# PROB_S7CAS_Clock.net
KiCad netlist of a schematic drawn in Altium Designer
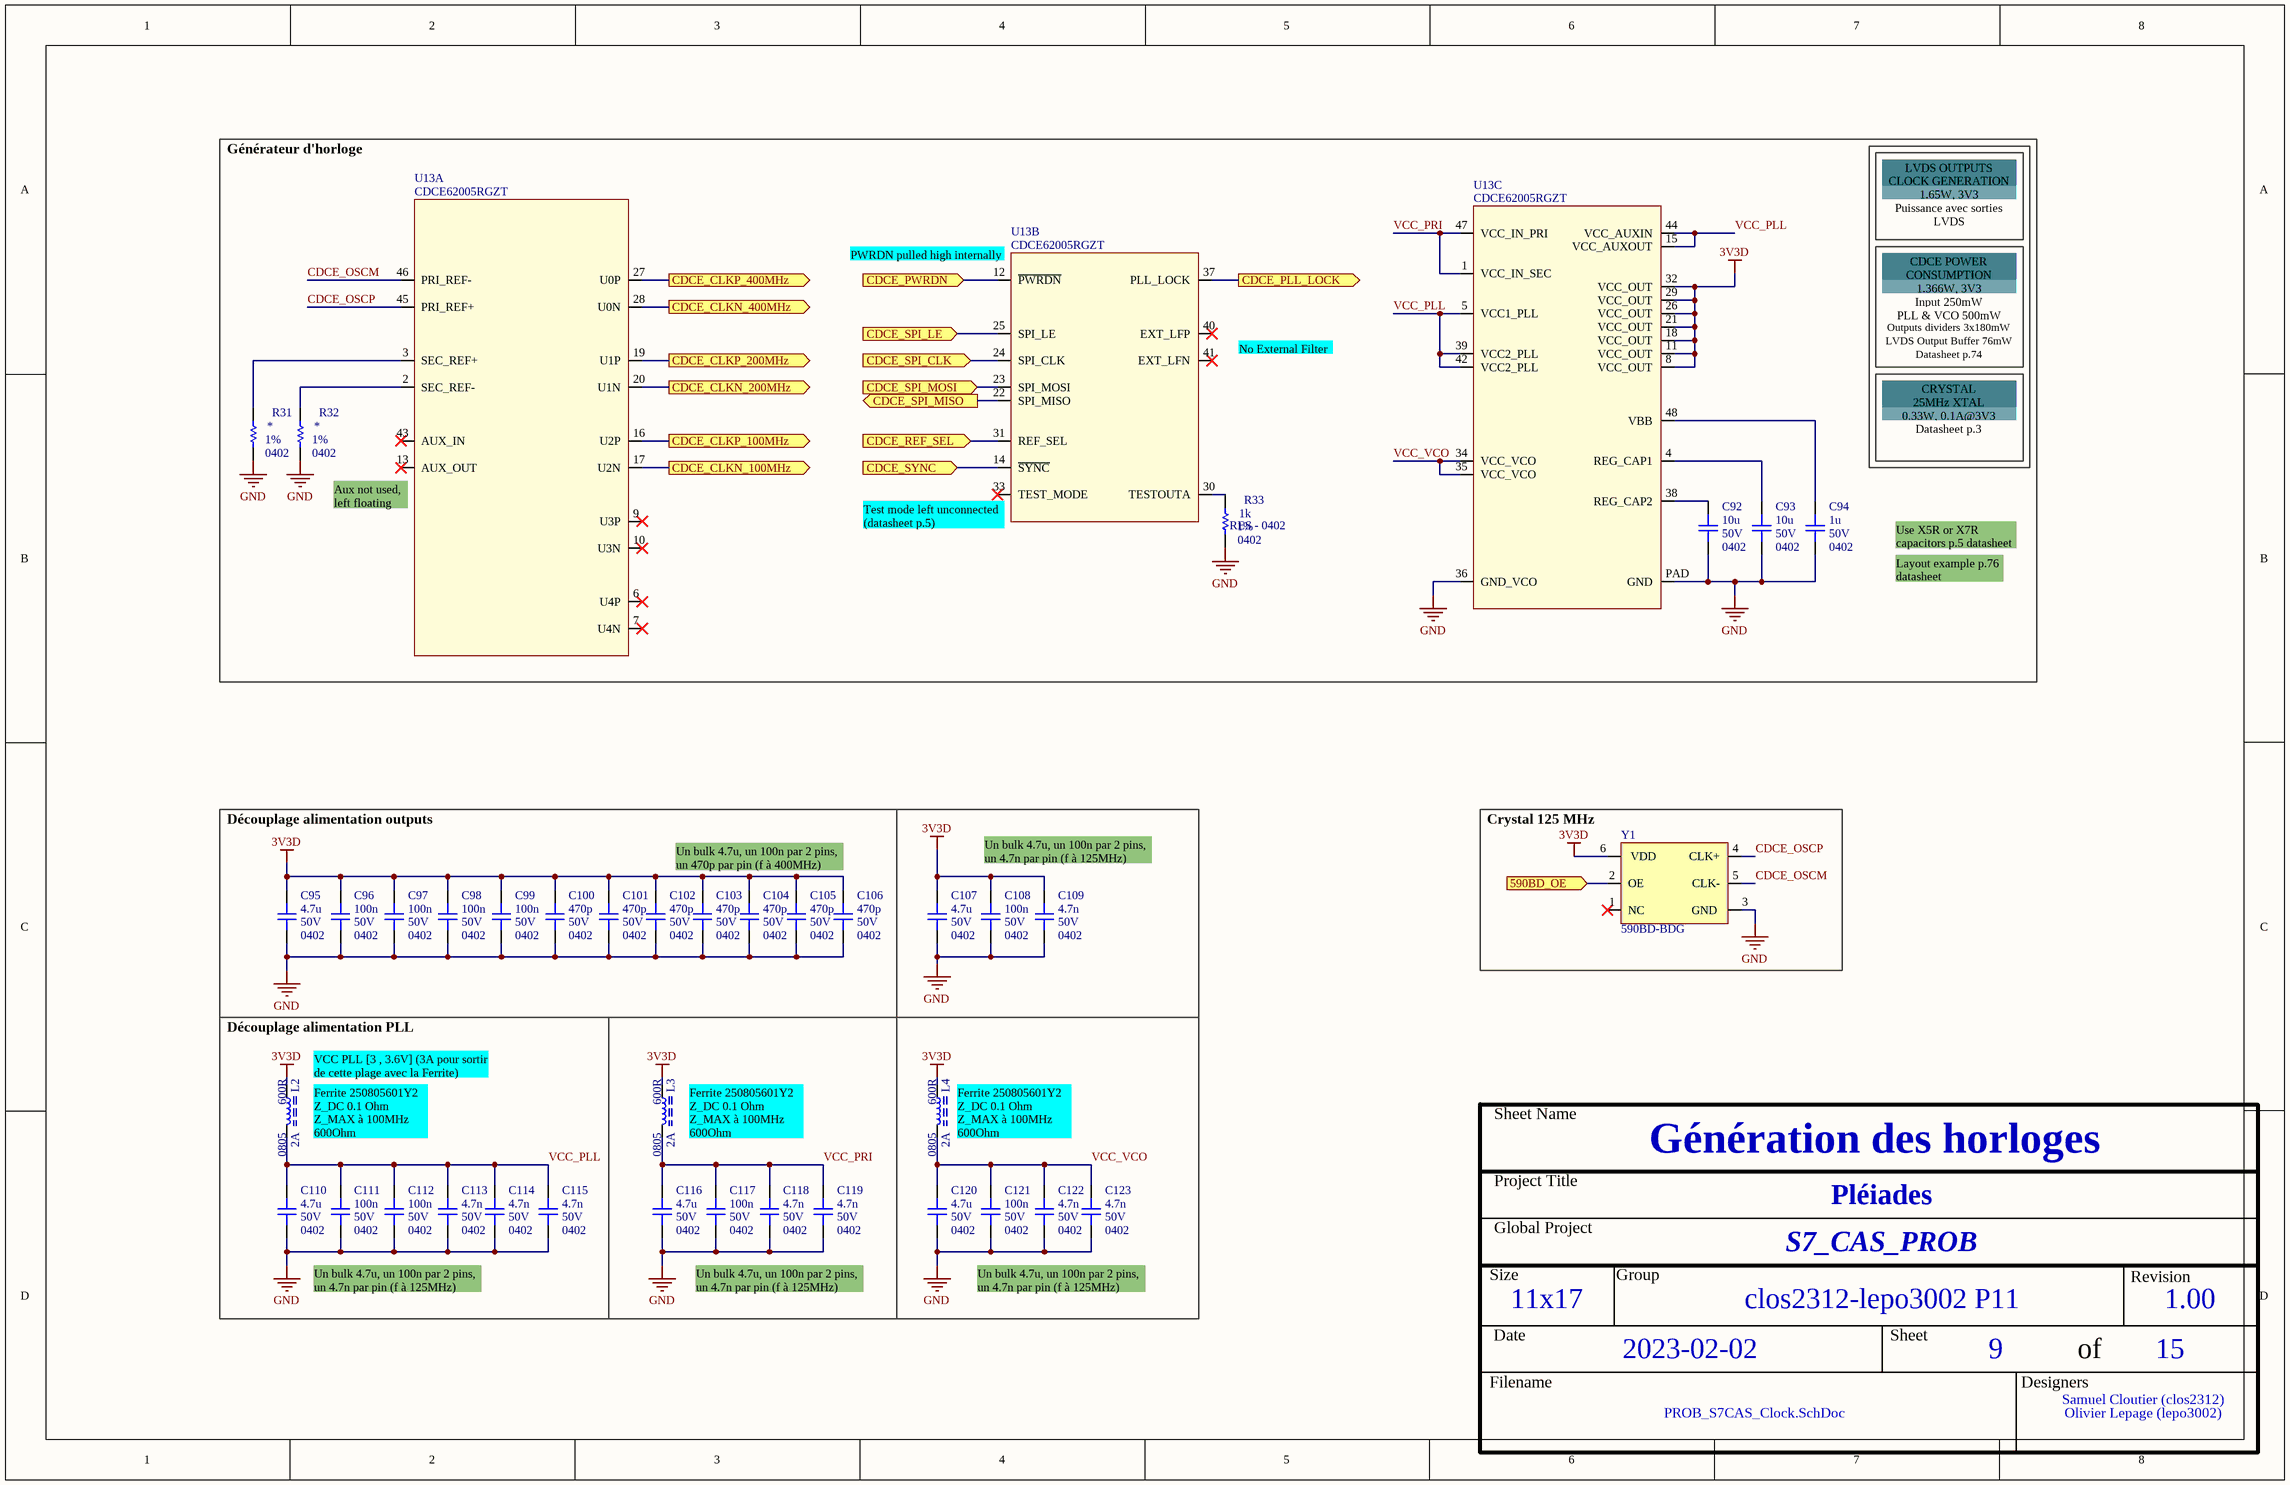
[diagram p0: PROB_S7CAS_Clock.SchDoc]

(export (version "E")
  (design (tool "Eeschema 10.0.6"))
  (components
    (comp (ref "C92")
      (value "10u")
      (footprint "CAP_0402")
      (description "CAP - 0402")
      (fields
        (field (name "VOLTAGE") "50V")
        (field (name "PACKAGE") "0402")
        (field (name "CREATEDBY") "Jonathan Bouchard")
      )
      (libsource (lib "S7CAS_LIB2021") (part "CAP - 0402"))
    )
    (comp (ref "C93")
      (value "10u")
      (footprint "CAP_0402")
      (description "CAP - 0402")
      (fields
        (field (name "VOLTAGE") "50V")
        (field (name "PACKAGE") "0402")
        (field (name "CREATEDBY") "Jonathan Bouchard")
      )
      (libsource (lib "S7CAS_LIB2021") (part "CAP - 0402"))
    )
    (comp (ref "C94")
      (value "1u")
      (footprint "CAP_0402")
      (description "CAP - 0402")
      (fields
        (field (name "VOLTAGE") "50V")
        (field (name "PACKAGE") "0402")
        (field (name "CREATEDBY") "Jonathan Bouchard")
      )
      (libsource (lib "S7CAS_LIB2021") (part "CAP - 0402"))
    )
    (comp (ref "C95")
      (value "4.7u")
      (footprint "CAP_0402")
      (description "CAP - 0402")
      (fields
        (field (name "VOLTAGE") "50V")
        (field (name "PACKAGE") "0402")
        (field (name "CREATEDBY") "Jonathan Bouchard")
      )
      (libsource (lib "S7CAS_LIB2021") (part "CAP - 0402"))
    )
    (comp (ref "C96")
      (value "100n")
      (footprint "CAP_0402")
      (description "CAP - 0402")
      (fields
        (field (name "VOLTAGE") "50V")
        (field (name "PACKAGE") "0402")
        (field (name "CREATEDBY") "Jonathan Bouchard")
      )
      (libsource (lib "S7CAS_LIB2021") (part "CAP - 0402"))
    )
    (comp (ref "C97")
      (value "100n")
      (footprint "CAP_0402")
      (description "CAP - 0402")
      (fields
        (field (name "VOLTAGE") "50V")
        (field (name "PACKAGE") "0402")
        (field (name "CREATEDBY") "Jonathan Bouchard")
      )
      (libsource (lib "S7CAS_LIB2021") (part "CAP - 0402"))
    )
    (comp (ref "C98")
      (value "100n")
      (footprint "CAP_0402")
      (description "CAP - 0402")
      (fields
        (field (name "VOLTAGE") "50V")
        (field (name "PACKAGE") "0402")
        (field (name "CREATEDBY") "Jonathan Bouchard")
      )
      (libsource (lib "S7CAS_LIB2021") (part "CAP - 0402"))
    )
    (comp (ref "C99")
      (value "100n")
      (footprint "CAP_0402")
      (description "CAP - 0402")
      (fields
        (field (name "VOLTAGE") "50V")
        (field (name "PACKAGE") "0402")
        (field (name "CREATEDBY") "Jonathan Bouchard")
      )
      (libsource (lib "S7CAS_LIB2021") (part "CAP - 0402"))
    )
    (comp (ref "C100")
      (value "470p")
      (footprint "CAP_0402")
      (description "CAP - 0402")
      (fields
        (field (name "VOLTAGE") "50V")
        (field (name "PACKAGE") "0402")
        (field (name "CREATEDBY") "Jonathan Bouchard")
      )
      (libsource (lib "S7CAS_LIB2021") (part "CAP - 0402"))
    )
    (comp (ref "C101")
      (value "470p")
      (footprint "CAP_0402")
      (description "CAP - 0402")
      (fields
        (field (name "VOLTAGE") "50V")
        (field (name "PACKAGE") "0402")
        (field (name "CREATEDBY") "Jonathan Bouchard")
      )
      (libsource (lib "S7CAS_LIB2021") (part "CAP - 0402"))
    )
    (comp (ref "C102")
      (value "470p")
      (footprint "CAP_0402")
      (description "CAP - 0402")
      (fields
        (field (name "VOLTAGE") "50V")
        (field (name "PACKAGE") "0402")
        (field (name "CREATEDBY") "Jonathan Bouchard")
      )
      (libsource (lib "S7CAS_LIB2021") (part "CAP - 0402"))
    )
    (comp (ref "C103")
      (value "470p")
      (footprint "CAP_0402")
      (description "CAP - 0402")
      (fields
        (field (name "VOLTAGE") "50V")
        (field (name "PACKAGE") "0402")
        (field (name "CREATEDBY") "Jonathan Bouchard")
      )
      (libsource (lib "S7CAS_LIB2021") (part "CAP - 0402"))
    )
    (comp (ref "C104")
      (value "470p")
      (footprint "CAP_0402")
      (description "CAP - 0402")
      (fields
        (field (name "VOLTAGE") "50V")
        (field (name "PACKAGE") "0402")
        (field (name "CREATEDBY") "Jonathan Bouchard")
      )
      (libsource (lib "S7CAS_LIB2021") (part "CAP - 0402"))
    )
    (comp (ref "C105")
      (value "470p")
      (footprint "CAP_0402")
      (description "CAP - 0402")
      (fields
        (field (name "VOLTAGE") "50V")
        (field (name "PACKAGE") "0402")
        (field (name "CREATEDBY") "Jonathan Bouchard")
      )
      (libsource (lib "S7CAS_LIB2021") (part "CAP - 0402"))
    )
    (comp (ref "C106")
      (value "470p")
      (footprint "CAP_0402")
      (description "CAP - 0402")
      (fields
        (field (name "VOLTAGE") "50V")
        (field (name "PACKAGE") "0402")
        (field (name "CREATEDBY") "Jonathan Bouchard")
      )
      (libsource (lib "S7CAS_LIB2021") (part "CAP - 0402"))
    )
    (comp (ref "C107")
      (value "4.7u")
      (footprint "CAP_0402")
      (description "CAP - 0402")
      (fields
        (field (name "VOLTAGE") "50V")
        (field (name "PACKAGE") "0402")
        (field (name "CREATEDBY") "Jonathan Bouchard")
      )
      (libsource (lib "S7CAS_LIB2021") (part "CAP - 0402"))
    )
    (comp (ref "C108")
      (value "100n")
      (footprint "CAP_0402")
      (description "CAP - 0402")
      (fields
        (field (name "VOLTAGE") "50V")
        (field (name "PACKAGE") "0402")
        (field (name "CREATEDBY") "Jonathan Bouchard")
      )
      (libsource (lib "S7CAS_LIB2021") (part "CAP - 0402"))
    )
    (comp (ref "C109")
      (value "4.7n")
      (footprint "CAP_0402")
      (description "CAP - 0402")
      (fields
        (field (name "VOLTAGE") "50V")
        (field (name "PACKAGE") "0402")
        (field (name "CREATEDBY") "Jonathan Bouchard")
      )
      (libsource (lib "S7CAS_LIB2021") (part "CAP - 0402"))
    )
    (comp (ref "C110")
      (value "4.7u")
      (footprint "CAP_0402")
      (description "CAP - 0402")
      (fields
        (field (name "VOLTAGE") "50V")
        (field (name "PACKAGE") "0402")
        (field (name "CREATEDBY") "Jonathan Bouchard")
      )
      (libsource (lib "S7CAS_LIB2021") (part "CAP - 0402"))
    )
    (comp (ref "C111")
      (value "100n")
      (footprint "CAP_0402")
      (description "CAP - 0402")
      (fields
        (field (name "VOLTAGE") "50V")
        (field (name "PACKAGE") "0402")
        (field (name "CREATEDBY") "Jonathan Bouchard")
      )
      (libsource (lib "S7CAS_LIB2021") (part "CAP - 0402"))
    )
    (comp (ref "C112")
      (value "100n")
      (footprint "CAP_0402")
      (description "CAP - 0402")
      (fields
        (field (name "VOLTAGE") "50V")
        (field (name "PACKAGE") "0402")
        (field (name "CREATEDBY") "Jonathan Bouchard")
      )
      (libsource (lib "S7CAS_LIB2021") (part "CAP - 0402"))
    )
    (comp (ref "C113")
      (value "4.7n")
      (footprint "CAP_0402")
      (description "CAP - 0402")
      (fields
        (field (name "VOLTAGE") "50V")
        (field (name "PACKAGE") "0402")
        (field (name "CREATEDBY") "Jonathan Bouchard")
      )
      (libsource (lib "S7CAS_LIB2021") (part "CAP - 0402"))
    )
    (comp (ref "C114")
      (value "4.7n")
      (footprint "CAP_0402")
      (description "CAP - 0402")
      (fields
        (field (name "VOLTAGE") "50V")
        (field (name "PACKAGE") "0402")
        (field (name "CREATEDBY") "Jonathan Bouchard")
      )
      (libsource (lib "S7CAS_LIB2021") (part "CAP - 0402"))
    )
    (comp (ref "C115")
      (value "4.7n")
      (footprint "CAP_0402")
      (description "CAP - 0402")
      (fields
        (field (name "VOLTAGE") "50V")
        (field (name "PACKAGE") "0402")
        (field (name "CREATEDBY") "Jonathan Bouchard")
      )
      (libsource (lib "S7CAS_LIB2021") (part "CAP - 0402"))
    )
    (comp (ref "C116")
      (value "4.7u")
      (footprint "CAP_0402")
      (description "CAP - 0402")
      (fields
        (field (name "VOLTAGE") "50V")
        (field (name "PACKAGE") "0402")
        (field (name "CREATEDBY") "Jonathan Bouchard")
      )
      (libsource (lib "S7CAS_LIB2021") (part "CAP - 0402"))
    )
    (comp (ref "C117")
      (value "100n")
      (footprint "CAP_0402")
      (description "CAP - 0402")
      (fields
        (field (name "VOLTAGE") "50V")
        (field (name "PACKAGE") "0402")
        (field (name "CREATEDBY") "Jonathan Bouchard")
      )
      (libsource (lib "S7CAS_LIB2021") (part "CAP - 0402"))
    )
    (comp (ref "C118")
      (value "4.7n")
      (footprint "CAP_0402")
      (description "CAP - 0402")
      (fields
        (field (name "VOLTAGE") "50V")
        (field (name "PACKAGE") "0402")
        (field (name "CREATEDBY") "Jonathan Bouchard")
      )
      (libsource (lib "S7CAS_LIB2021") (part "CAP - 0402"))
    )
    (comp (ref "C119")
      (value "4.7n")
      (footprint "CAP_0402")
      (description "CAP - 0402")
      (fields
        (field (name "VOLTAGE") "50V")
        (field (name "PACKAGE") "0402")
        (field (name "CREATEDBY") "Jonathan Bouchard")
      )
      (libsource (lib "S7CAS_LIB2021") (part "CAP - 0402"))
    )
    (comp (ref "C120")
      (value "4.7u")
      (footprint "CAP_0402")
      (description "CAP - 0402")
      (fields
        (field (name "VOLTAGE") "50V")
        (field (name "PACKAGE") "0402")
        (field (name "CREATEDBY") "Jonathan Bouchard")
      )
      (libsource (lib "S7CAS_LIB2021") (part "CAP - 0402"))
    )
    (comp (ref "C121")
      (value "100n")
      (footprint "CAP_0402")
      (description "CAP - 0402")
      (fields
        (field (name "VOLTAGE") "50V")
        (field (name "PACKAGE") "0402")
        (field (name "CREATEDBY") "Jonathan Bouchard")
      )
      (libsource (lib "S7CAS_LIB2021") (part "CAP - 0402"))
    )
    (comp (ref "C122")
      (value "4.7n")
      (footprint "CAP_0402")
      (description "CAP - 0402")
      (fields
        (field (name "VOLTAGE") "50V")
        (field (name "PACKAGE") "0402")
        (field (name "CREATEDBY") "Jonathan Bouchard")
      )
      (libsource (lib "S7CAS_LIB2021") (part "CAP - 0402"))
    )
    (comp (ref "C123")
      (value "4.7n")
      (footprint "CAP_0402")
      (description "CAP - 0402")
      (fields
        (field (name "VOLTAGE") "50V")
        (field (name "PACKAGE") "0402")
        (field (name "CREATEDBY") "Jonathan Bouchard")
      )
      (libsource (lib "S7CAS_LIB2021") (part "CAP - 0402"))
    )
    (comp (ref "L2")
      (value "600R")
      (footprint "FER_0402")
      (description "FER - 0402")
      (fields
        (field (name "CURRENT") "2A")
        (field (name "PACKAGE") "0805")
        (field (name "CREATEDBY") "Jonathan Bouchard")
      )
      (libsource (lib "S7CAS_LIB2021") (part "FER - 0402"))
    )
    (comp (ref "L3")
      (value "600R")
      (footprint "FER_0402")
      (description "FER - 0402")
      (fields
        (field (name "CURRENT") "2A")
        (field (name "PACKAGE") "0805")
        (field (name "CREATEDBY") "Jonathan Bouchard")
      )
      (libsource (lib "S7CAS_LIB2021") (part "FER - 0402"))
    )
    (comp (ref "L4")
      (value "600R")
      (footprint "FER_0402")
      (description "FER - 0402")
      (fields
        (field (name "CURRENT") "2A")
        (field (name "PACKAGE") "0805")
        (field (name "CREATEDBY") "Jonathan Bouchard")
      )
      (libsource (lib "S7CAS_LIB2021") (part "FER - 0402"))
    )
    (comp (ref "R31")
      (value "RES - 0402")
      (footprint "RES_0402")
      (fields
        (field (name "VOLTAGE") "50V")
        (field (name "POWER") "1/16W")
        (field (name "PACKAGE") "0402")
        (field (name "PRECISION") "1%")
        (field (name "ALTIUM_VALUE") "*")
        (field (name "CREATEDBY") "Jonathan Bouchard")
      )
      (libsource (lib "S7CAS_LIB2021") (part "RES - 0402"))
    )
    (comp (ref "R32")
      (value "RES - 0402")
      (footprint "RES_0402")
      (fields
        (field (name "VOLTAGE") "50V")
        (field (name "POWER") "1/16W")
        (field (name "PACKAGE") "0402")
        (field (name "PRECISION") "1%")
        (field (name "ALTIUM_VALUE") "*")
        (field (name "CREATEDBY") "Jonathan Bouchard")
      )
      (libsource (lib "S7CAS_LIB2021") (part "RES - 0402"))
    )
    (comp (ref "R33")
      (value "RES - 0402")
      (footprint "RES_0402")
      (fields
        (field (name "PACKAGE") "0402")
        (field (name "PRECISION") "1%")
        (field (name "ALTIUM_VALUE") "1k")
        (field (name "VOLTAGE") "50V")
        (field (name "POWER") "1/16W")
        (field (name "CREATEDBY") "Jonathan Bouchard")
      )
      (libsource (lib "Université de Sherbrooke") (part "RES - 1210"))
    )
    (comp (ref "U13")
      (value "CDCE62005RGZT")
      (footprint "TIM_CDCE62005RGZT")
      (description "TIM - CLK SYNTH JITTER CLEANER 3:5 - QFN-48")
      (fields
        (field (name "VOLTAGE") "3 V ~ 3.6 V")
        (field (name "MFG") "Texas Instruments")
        (field (name "CREATEDBY") "Jonathan Bouchard")
      )
      (libsource (lib "S7CAS_LIB2021") (part "TIM_CDCE62005RGZT"))
    )
    (comp (ref "Y1")
      (value "590BD-BDG")
      (footprint "OSC_590BD-BDG")
      (description "TIM - OSC PROG 125MHz ~ 214.999MHz LVDS 3.3V 7PPM EN/DS - 6-SMD")
      (fields
        (field (name "CREATEDBY/DATE") "from 590BD-CDG")
        (field (name "VERIFIEDBY") "Caroline Paulin / 3/10/2019")
      )
      (libsource (lib "S7CAS_LIB2021") (part "OSC_590BD-BDG"))
    )
  )
  (nets
    (net (code "1") (name "/590BD_OE") (class "Default")
      (node (ref "Y1") (pin "2") (pinfunction "OE_2") (pintype "passive"))
    )
    (net (code "2") (name "/CDCE_CLKN_100MHz") (class "Default")
      (node (ref "U13") (pin "17") (pinfunction "U2N_17") (pintype "passive"))
    )
    (net (code "3") (name "/CDCE_CLKN_200MHz") (class "Default")
      (node (ref "U13") (pin "20") (pinfunction "U1N_20") (pintype "passive"))
    )
    (net (code "4") (name "/CDCE_CLKN_400MHz") (class "Default")
      (node (ref "U13") (pin "28") (pinfunction "U0N_28") (pintype "passive"))
    )
    (net (code "5") (name "/CDCE_CLKP_100MHz") (class "Default")
      (node (ref "U13") (pin "16") (pinfunction "U2P_16") (pintype "passive"))
    )
    (net (code "6") (name "/CDCE_CLKP_200MHz") (class "Default")
      (node (ref "U13") (pin "19") (pinfunction "U1P_19") (pintype "passive"))
    )
    (net (code "7") (name "/CDCE_CLKP_400MHz") (class "Default")
      (node (ref "U13") (pin "27") (pinfunction "U0P_27") (pintype "passive"))
    )
    (net (code "8") (name "/CDCE_OSCM") (class "Default")
      (node (ref "U13") (pin "46") (pinfunction "PRI_REF-_46") (pintype "passive"))
      (node (ref "Y1") (pin "5") (pinfunction "CLK-_5") (pintype "passive"))
    )
    (net (code "9") (name "/CDCE_OSCP") (class "Default")
      (node (ref "U13") (pin "45") (pinfunction "PRI_REF+_45") (pintype "passive"))
      (node (ref "Y1") (pin "4") (pinfunction "CLK+_4") (pintype "passive"))
    )
    (net (code "10") (name "/CDCE_PLL_LOCK") (class "Default")
      (node (ref "U13") (pin "37") (pinfunction "PLL_LOCK_37") (pintype "passive"))
    )
    (net (code "11") (name "/CDCE_PWRDN") (class "Default")
      (node (ref "U13") (pin "12") (pinfunction "~{PWRDN}_12") (pintype "passive"))
    )
    (net (code "12") (name "/CDCE_REF_SEL") (class "Default")
      (node (ref "U13") (pin "31") (pinfunction "REF_SEL_31") (pintype "passive"))
    )
    (net (code "13") (name "/CDCE_SPI_CLK") (class "Default")
      (node (ref "U13") (pin "24") (pinfunction "SPI_CLK_24") (pintype "passive"))
    )
    (net (code "14") (name "/CDCE_SPI_LE") (class "Default")
      (node (ref "U13") (pin "25") (pinfunction "SPI_LE_25") (pintype "passive"))
    )
    (net (code "15") (name "/CDCE_SPI_MISO") (class "Default")
      (node (ref "U13") (pin "22") (pinfunction "SPI_MISO_22") (pintype "passive"))
    )
    (net (code "16") (name "/CDCE_SPI_MOSI") (class "Default")
      (node (ref "U13") (pin "23") (pinfunction "SPI_MOSI_23") (pintype "passive"))
    )
    (net (code "17") (name "/CDCE_SYNC") (class "Default")
      (node (ref "U13") (pin "14") (pinfunction "~{SYNC}_14") (pintype "passive"))
    )
    (net (code "18") (name "/VCC_PLL") (class "Default")
      (node (ref "C110") (pin "2") (pinfunction "2_2") (pintype "passive"))
      (node (ref "C111") (pin "2") (pinfunction "2_2") (pintype "passive"))
      (node (ref "C112") (pin "2") (pinfunction "2_2") (pintype "passive"))
      (node (ref "C113") (pin "2") (pinfunction "2_2") (pintype "passive"))
      (node (ref "C114") (pin "2") (pinfunction "2_2") (pintype "passive"))
      (node (ref "C115") (pin "2") (pinfunction "2_2") (pintype "passive"))
      (node (ref "L2") (pin "1") (pinfunction "1_1") (pintype "passive"))
      (node (ref "U13") (pin "15") (pinfunction "VCC_AUXOUT_15") (pintype "passive"))
      (node (ref "U13") (pin "39") (pinfunction "VCC2_PLL_39") (pintype "passive"))
      (node (ref "U13") (pin "42") (pinfunction "VCC2_PLL_42") (pintype "passive"))
      (node (ref "U13") (pin "44") (pinfunction "VCC_AUXIN_44") (pintype "passive"))
      (node (ref "U13") (pin "5") (pinfunction "VCC1_PLL_5") (pintype "passive"))
    )
    (net (code "19") (name "/VCC_PRI") (class "Default")
      (node (ref "C116") (pin "2") (pinfunction "2_2") (pintype "passive"))
      (node (ref "C117") (pin "2") (pinfunction "2_2") (pintype "passive"))
      (node (ref "C118") (pin "2") (pinfunction "2_2") (pintype "passive"))
      (node (ref "C119") (pin "2") (pinfunction "2_2") (pintype "passive"))
      (node (ref "L3") (pin "1") (pinfunction "1_1") (pintype "passive"))
      (node (ref "U13") (pin "1") (pinfunction "VCC_IN_SEC_1") (pintype "passive"))
      (node (ref "U13") (pin "47") (pinfunction "VCC_IN_PRI_47") (pintype "passive"))
    )
    (net (code "20") (name "/VCC_VCO") (class "Default")
      (node (ref "C120") (pin "2") (pinfunction "2_2") (pintype "passive"))
      (node (ref "C121") (pin "2") (pinfunction "2_2") (pintype "passive"))
      (node (ref "C122") (pin "2") (pinfunction "2_2") (pintype "passive"))
      (node (ref "C123") (pin "2") (pinfunction "2_2") (pintype "passive"))
      (node (ref "L4") (pin "1") (pinfunction "1_1") (pintype "passive"))
      (node (ref "U13") (pin "34") (pinfunction "VCC_VCO_34") (pintype "passive"))
      (node (ref "U13") (pin "35") (pinfunction "VCC_VCO_35") (pintype "passive"))
    )
    (net (code "21") (name "3V3D") (class "Default")
      (node (ref "C100") (pin "2") (pinfunction "2_2") (pintype "passive"))
      (node (ref "C101") (pin "2") (pinfunction "2_2") (pintype "passive"))
      (node (ref "C102") (pin "2") (pinfunction "2_2") (pintype "passive"))
      (node (ref "C103") (pin "2") (pinfunction "2_2") (pintype "passive"))
      (node (ref "C104") (pin "2") (pinfunction "2_2") (pintype "passive"))
      (node (ref "C105") (pin "2") (pinfunction "2_2") (pintype "passive"))
      (node (ref "C106") (pin "2") (pinfunction "2_2") (pintype "passive"))
      (node (ref "C107") (pin "2") (pinfunction "2_2") (pintype "passive"))
      (node (ref "C108") (pin "2") (pinfunction "2_2") (pintype "passive"))
      (node (ref "C109") (pin "2") (pinfunction "2_2") (pintype "passive"))
      (node (ref "C95") (pin "2") (pinfunction "2_2") (pintype "passive"))
      (node (ref "C96") (pin "2") (pinfunction "2_2") (pintype "passive"))
      (node (ref "C97") (pin "2") (pinfunction "2_2") (pintype "passive"))
      (node (ref "C98") (pin "2") (pinfunction "2_2") (pintype "passive"))
      (node (ref "C99") (pin "2") (pinfunction "2_2") (pintype "passive"))
      (node (ref "L2") (pin "2") (pinfunction "2_2") (pintype "passive"))
      (node (ref "L3") (pin "2") (pinfunction "2_2") (pintype "passive"))
      (node (ref "L4") (pin "2") (pinfunction "2_2") (pintype "passive"))
      (node (ref "U13") (pin "11") (pinfunction "VCC_OUT_11") (pintype "passive"))
      (node (ref "U13") (pin "18") (pinfunction "VCC_OUT_18") (pintype "passive"))
      (node (ref "U13") (pin "21") (pinfunction "VCC_OUT_21") (pintype "passive"))
      (node (ref "U13") (pin "26") (pinfunction "VCC_OUT_26") (pintype "passive"))
      (node (ref "U13") (pin "29") (pinfunction "VCC_OUT_29") (pintype "passive"))
      (node (ref "U13") (pin "32") (pinfunction "VCC_OUT_32") (pintype "passive"))
      (node (ref "U13") (pin "8") (pinfunction "VCC_OUT_8") (pintype "passive"))
      (node (ref "Y1") (pin "6") (pinfunction "VDD_6") (pintype "passive"))
    )
    (net (code "22") (name "GND") (class "Default")
      (node (ref "C100") (pin "1") (pinfunction "1_1") (pintype "passive"))
      (node (ref "C101") (pin "1") (pinfunction "1_1") (pintype "passive"))
      (node (ref "C102") (pin "1") (pinfunction "1_1") (pintype "passive"))
      (node (ref "C103") (pin "1") (pinfunction "1_1") (pintype "passive"))
      (node (ref "C104") (pin "1") (pinfunction "1_1") (pintype "passive"))
      (node (ref "C105") (pin "1") (pinfunction "1_1") (pintype "passive"))
      (node (ref "C106") (pin "1") (pinfunction "1_1") (pintype "passive"))
      (node (ref "C107") (pin "1") (pinfunction "1_1") (pintype "passive"))
      (node (ref "C108") (pin "1") (pinfunction "1_1") (pintype "passive"))
      (node (ref "C109") (pin "1") (pinfunction "1_1") (pintype "passive"))
      (node (ref "C110") (pin "1") (pinfunction "1_1") (pintype "passive"))
      (node (ref "C111") (pin "1") (pinfunction "1_1") (pintype "passive"))
      (node (ref "C112") (pin "1") (pinfunction "1_1") (pintype "passive"))
      (node (ref "C113") (pin "1") (pinfunction "1_1") (pintype "passive"))
      (node (ref "C114") (pin "1") (pinfunction "1_1") (pintype "passive"))
      (node (ref "C115") (pin "1") (pinfunction "1_1") (pintype "passive"))
      (node (ref "C116") (pin "1") (pinfunction "1_1") (pintype "passive"))
      (node (ref "C117") (pin "1") (pinfunction "1_1") (pintype "passive"))
      (node (ref "C118") (pin "1") (pinfunction "1_1") (pintype "passive"))
      (node (ref "C119") (pin "1") (pinfunction "1_1") (pintype "passive"))
      (node (ref "C120") (pin "1") (pinfunction "1_1") (pintype "passive"))
      (node (ref "C121") (pin "1") (pinfunction "1_1") (pintype "passive"))
      (node (ref "C122") (pin "1") (pinfunction "1_1") (pintype "passive"))
      (node (ref "C123") (pin "1") (pinfunction "1_1") (pintype "passive"))
      (node (ref "C92") (pin "1") (pinfunction "1_1") (pintype "passive"))
      (node (ref "C93") (pin "1") (pinfunction "1_1") (pintype "passive"))
      (node (ref "C94") (pin "1") (pinfunction "1_1") (pintype "passive"))
      (node (ref "C95") (pin "1") (pinfunction "1_1") (pintype "passive"))
      (node (ref "C96") (pin "1") (pinfunction "1_1") (pintype "passive"))
      (node (ref "C97") (pin "1") (pinfunction "1_1") (pintype "passive"))
      (node (ref "C98") (pin "1") (pinfunction "1_1") (pintype "passive"))
      (node (ref "C99") (pin "1") (pinfunction "1_1") (pintype "passive"))
      (node (ref "R31") (pin "1") (pinfunction "1_1") (pintype "passive"))
      (node (ref "R32") (pin "1") (pinfunction "1_1") (pintype "passive"))
      (node (ref "R33") (pin "1") (pinfunction "1_1") (pintype "passive"))
      (node (ref "U13") (pin "36") (pinfunction "GND_VCO_36") (pintype "passive"))
      (node (ref "U13") (pin "PAD") (pinfunction "GND_PAD") (pintype "passive"))
      (node (ref "Y1") (pin "3") (pinfunction "GND_3") (pintype "passive"))
    )
    (net (code "23") (name "Net-(U13A-SEC_REF+)") (class "Default")
      (node (ref "R31") (pin "2") (pinfunction "2_2") (pintype "passive"))
      (node (ref "U13") (pin "3") (pinfunction "SEC_REF+_3") (pintype "passive"))
    )
    (net (code "24") (name "Net-(U13A-SEC_REF-)") (class "Default")
      (node (ref "R32") (pin "2") (pinfunction "2_2") (pintype "passive"))
      (node (ref "U13") (pin "2") (pinfunction "SEC_REF-_2") (pintype "passive"))
    )
    (net (code "25") (name "Net-(U13B-TESTOUTA)") (class "Default")
      (node (ref "R33") (pin "2") (pinfunction "2_2") (pintype "passive"))
      (node (ref "U13") (pin "30") (pinfunction "TESTOUTA_30") (pintype "passive"))
    )
    (net (code "26") (name "Net-(U13C-REG_CAP1)") (class "Default")
      (node (ref "C93") (pin "2") (pinfunction "2_2") (pintype "passive"))
      (node (ref "U13") (pin "4") (pinfunction "REG_CAP1_4") (pintype "passive"))
    )
    (net (code "27") (name "Net-(U13C-REG_CAP2)") (class "Default")
      (node (ref "C92") (pin "2") (pinfunction "2_2") (pintype "passive"))
      (node (ref "U13") (pin "38") (pinfunction "REG_CAP2_38") (pintype "passive"))
    )
    (net (code "28") (name "Net-(U13C-VBB)") (class "Default")
      (node (ref "C94") (pin "2") (pinfunction "2_2") (pintype "passive"))
      (node (ref "U13") (pin "48") (pinfunction "VBB_48") (pintype "passive"))
    )
    (net (code "29") (name "unconnected-(U13A-AUX_IN-Pad43)") (class "Default")
      (node (ref "U13") (pin "43") (pinfunction "AUX_IN_43") (pintype "passive+no_connect"))
    )
    (net (code "30") (name "unconnected-(U13A-AUX_OUT-Pad13)") (class "Default")
      (node (ref "U13") (pin "13") (pinfunction "AUX_OUT_13") (pintype "passive+no_connect"))
    )
    (net (code "31") (name "unconnected-(U13A-U3N-Pad10)") (class "Default")
      (node (ref "U13") (pin "10") (pinfunction "U3N_10") (pintype "passive+no_connect"))
    )
    (net (code "32") (name "unconnected-(U13A-U3P-Pad9)") (class "Default")
      (node (ref "U13") (pin "9") (pinfunction "U3P_9") (pintype "passive+no_connect"))
    )
    (net (code "33") (name "unconnected-(U13A-U4N-Pad7)") (class "Default")
      (node (ref "U13") (pin "7") (pinfunction "U4N_7") (pintype "passive+no_connect"))
    )
    (net (code "34") (name "unconnected-(U13A-U4P-Pad6)") (class "Default")
      (node (ref "U13") (pin "6") (pinfunction "U4P_6") (pintype "passive+no_connect"))
    )
    (net (code "35") (name "unconnected-(U13B-EXT_LFN-Pad41)") (class "Default")
      (node (ref "U13") (pin "41") (pinfunction "EXT_LFN_41") (pintype "passive+no_connect"))
    )
    (net (code "36") (name "unconnected-(U13B-EXT_LFP-Pad40)") (class "Default")
      (node (ref "U13") (pin "40") (pinfunction "EXT_LFP_40") (pintype "passive+no_connect"))
    )
    (net (code "37") (name "unconnected-(U13B-TEST_MODE-Pad33)") (class "Default")
      (node (ref "U13") (pin "33") (pinfunction "TEST_MODE_33") (pintype "passive+no_connect"))
    )
    (net (code "38") (name "unconnected-(Y1-NC-Pad1)") (class "Default")
      (node (ref "Y1") (pin "1") (pinfunction "NC_1") (pintype "passive+no_connect"))
    )
  )
)
